# watch_v1_flex_parts_test-rotated.net
KiCad netlist of a schematic drawn in EAGLE
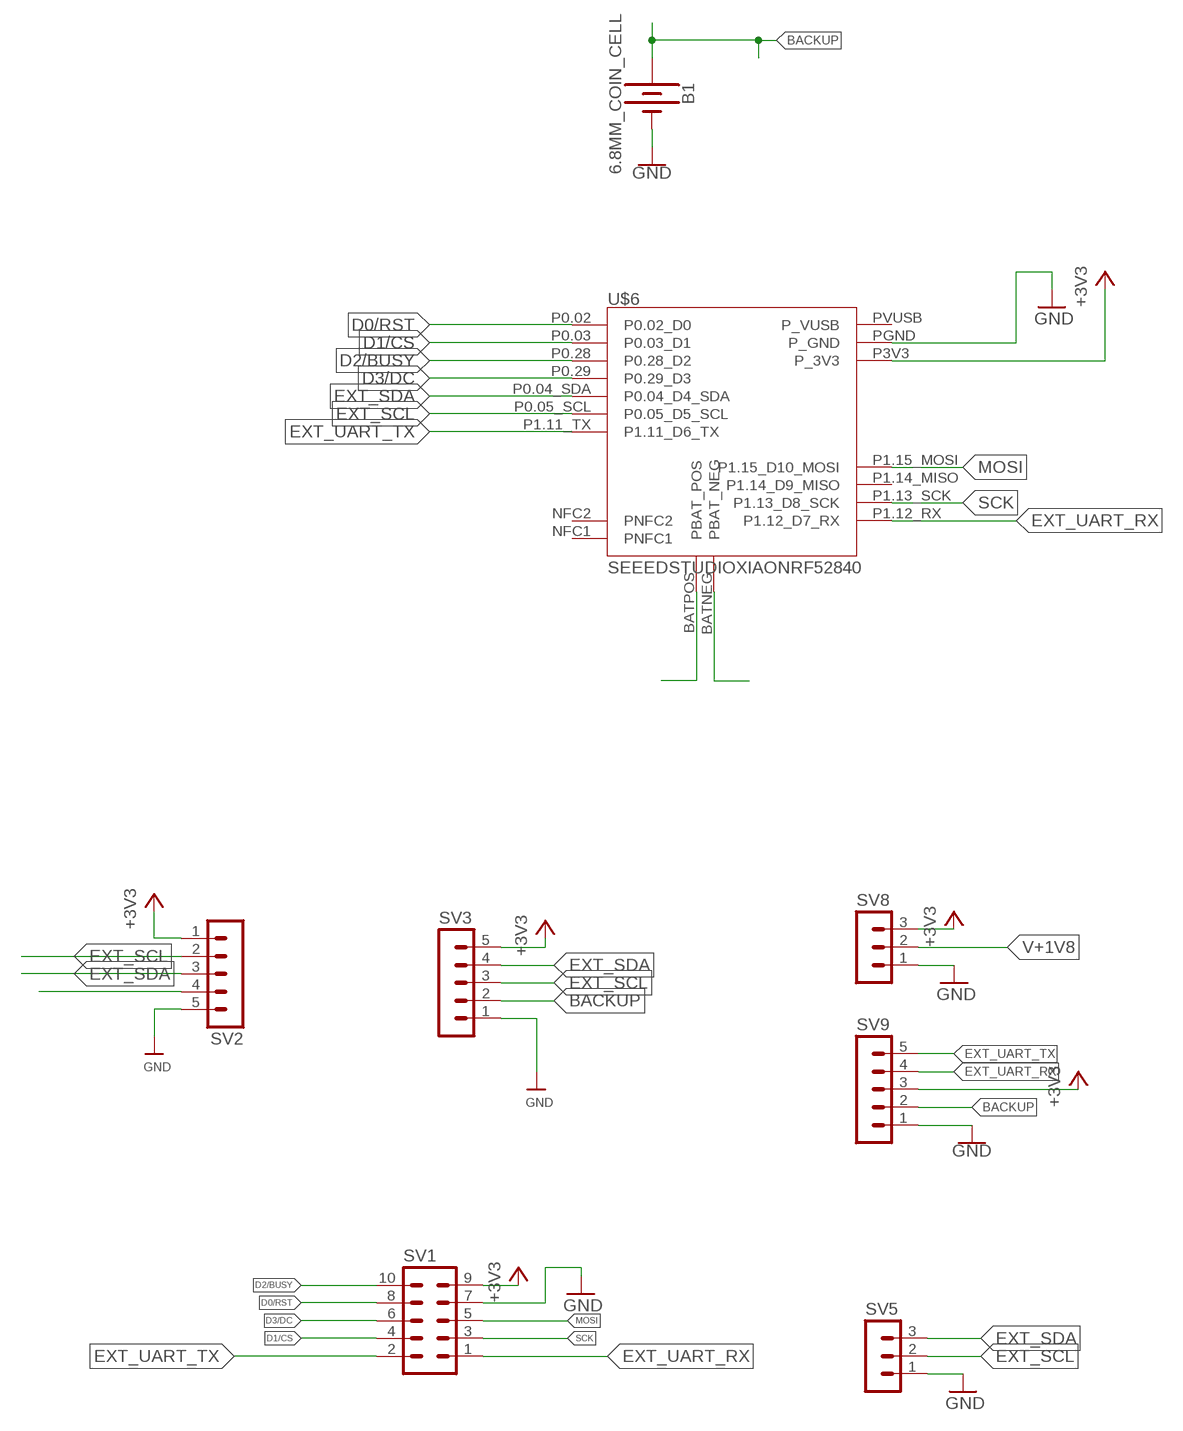
[diagram p0: schematic, sheet 1]

(export (version "E")
  (design (tool "Eeschema 10.0.6"))
  (components
    (comp (ref "B1")
      (value "6.8MM_COIN_CELL")
      (footprint "eagle-import:ML414H_IV01E")
      (libsource (lib "eagle-import") (part "ML414H_IV01E_BATTERY"))
    )
    (comp (ref "SV1")
      (value "MA05-2")
      (footprint "eagle-import:MA05-2")
      (libsource (lib "eagle-import") (part "MA05-2"))
    )
    (comp (ref "SV2")
      (value "MA05-1")
      (footprint "eagle-import:MA05-1")
      (libsource (lib "eagle-import") (part "MA05-1"))
    )
    (comp (ref "SV3")
      (value "MA05-1")
      (footprint "eagle-import:MA05-1")
      (libsource (lib "eagle-import") (part "MA05-1"))
    )
    (comp (ref "SV5")
      (value "MA03-1")
      (footprint "eagle-import:MA03-1")
      (libsource (lib "eagle-import") (part "MA03-1"))
    )
    (comp (ref "SV8")
      (value "MA03-1")
      (footprint "eagle-import:MA03-1")
      (libsource (lib "eagle-import") (part "MA03-1"))
    )
    (comp (ref "SV9")
      (value "MA05-1")
      (footprint "eagle-import:MA05-1")
      (libsource (lib "eagle-import") (part "MA05-1"))
    )
    (comp (ref "U$6")
      (value "SEEEDSTUDIOXIAONRF52840")
      (footprint "eagle-import:SEEEDSTUDIOXIAONRF52840")
      (libsource (lib "eagle-import") (part "SEEEDSTUDIOXIAONRF52840"))
    )
  )
  (nets
    (net (code "1") (name "+3V3") (class "Default")
      (node (ref "SV1") (pin "9") (pinfunction "9_9") (pintype "passive"))
      (node (ref "SV2") (pin "1") (pinfunction "1_1") (pintype "passive"))
      (node (ref "SV3") (pin "5") (pinfunction "5_5") (pintype "passive"))
      (node (ref "SV8") (pin "3") (pinfunction "3_3") (pintype "passive"))
      (node (ref "SV9") (pin "3") (pinfunction "3_3") (pintype "passive"))
      (node (ref "U$6") (pin "P3V3") (pinfunction "P_3V3_P3V3") (pintype "bidirectional"))
    )
    (net (code "2") (name "BACKUP") (class "Default")
      (node (ref "B1") (pin "+") (pinfunction "+_+") (pintype "power_in"))
      (node (ref "SV3") (pin "2") (pinfunction "2_2") (pintype "passive"))
      (node (ref "SV9") (pin "2") (pinfunction "2_2") (pintype "passive"))
    )
    (net (code "3") (name "D0{slash}RST") (class "Default")
      (node (ref "SV1") (pin "8") (pinfunction "8_8") (pintype "passive"))
      (node (ref "U$6") (pin "P0.02") (pinfunction "P0.02_D0_P0.02") (pintype "bidirectional"))
    )
    (net (code "4") (name "D1{slash}CS") (class "Default")
      (node (ref "SV1") (pin "4") (pinfunction "4_4") (pintype "passive"))
      (node (ref "U$6") (pin "P0.03") (pinfunction "P0.03_D1_P0.03") (pintype "bidirectional"))
    )
    (net (code "5") (name "D2{slash}BUSY") (class "Default")
      (node (ref "SV1") (pin "10") (pinfunction "10_10") (pintype "passive"))
      (node (ref "U$6") (pin "P0.28") (pinfunction "P0.28_D2_P0.28") (pintype "bidirectional"))
    )
    (net (code "6") (name "D3{slash}DC") (class "Default")
      (node (ref "SV1") (pin "6") (pinfunction "6_6") (pintype "passive"))
      (node (ref "U$6") (pin "P0.29") (pinfunction "P0.29_D3_P0.29") (pintype "bidirectional"))
    )
    (net (code "7") (name "EXT_SCL") (class "Default")
      (node (ref "SV2") (pin "2") (pinfunction "2_2") (pintype "passive"))
      (node (ref "SV3") (pin "3") (pinfunction "3_3") (pintype "passive"))
      (node (ref "SV5") (pin "2") (pinfunction "2_2") (pintype "passive"))
      (node (ref "U$6") (pin "P0.05_SCL") (pinfunction "P0.05_D5_SCL_P0.05_SCL") (pintype "bidirectional"))
    )
    (net (code "8") (name "EXT_SDA") (class "Default")
      (node (ref "SV2") (pin "3") (pinfunction "3_3") (pintype "passive"))
      (node (ref "SV3") (pin "4") (pinfunction "4_4") (pintype "passive"))
      (node (ref "SV5") (pin "3") (pinfunction "3_3") (pintype "passive"))
      (node (ref "U$6") (pin "P0.04_SDA") (pinfunction "P0.04_D4_SDA_P0.04_SDA") (pintype "bidirectional"))
    )
    (net (code "9") (name "EXT_UART_RX") (class "Default")
      (node (ref "SV1") (pin "1") (pinfunction "1_1") (pintype "passive"))
      (node (ref "SV9") (pin "4") (pinfunction "4_4") (pintype "passive"))
      (node (ref "U$6") (pin "P1.12_RX") (pinfunction "P1.12_D7_RX_P1.12_RX") (pintype "bidirectional"))
    )
    (net (code "10") (name "EXT_UART_TX") (class "Default")
      (node (ref "SV1") (pin "2") (pinfunction "2_2") (pintype "passive"))
      (node (ref "SV9") (pin "5") (pinfunction "5_5") (pintype "passive"))
      (node (ref "U$6") (pin "P1.11_TX") (pinfunction "P1.11_D6_TX_P1.11_TX") (pintype "bidirectional"))
    )
    (net (code "11") (name "GND") (class "Default")
      (node (ref "B1") (pin "-") (pinfunction "-_-") (pintype "power_in"))
      (node (ref "SV1") (pin "7") (pinfunction "7_7") (pintype "passive"))
      (node (ref "SV2") (pin "5") (pinfunction "5_5") (pintype "passive"))
      (node (ref "SV3") (pin "1") (pinfunction "1_1") (pintype "passive"))
      (node (ref "SV5") (pin "1") (pinfunction "1_1") (pintype "passive"))
      (node (ref "SV8") (pin "1") (pinfunction "1_1") (pintype "passive"))
      (node (ref "SV9") (pin "1") (pinfunction "1_1") (pintype "passive"))
      (node (ref "U$6") (pin "PGND") (pinfunction "P_GND_PGND") (pintype "bidirectional"))
    )
    (net (code "12") (name "MOSI") (class "Default")
      (node (ref "SV1") (pin "5") (pinfunction "5_5") (pintype "passive"))
      (node (ref "U$6") (pin "P1.15_MOSI") (pinfunction "P1.15_D10_MOSI_P1.15_MOSI") (pintype "bidirectional"))
    )
    (net (code "13") (name "SCK") (class "Default")
      (node (ref "SV1") (pin "3") (pinfunction "3_3") (pintype "passive"))
      (node (ref "U$6") (pin "P1.13_SCK") (pinfunction "P1.13_D8_SCK_P1.13_SCK") (pintype "bidirectional"))
    )
    (net (code "14") (name "V+1V8") (class "Default")
      (node (ref "SV8") (pin "2") (pinfunction "2_2") (pintype "passive"))
    )
    (net (code "15") (name "unconnected-(SV2-Pad4)") (class "Default")
      (node (ref "SV2") (pin "4") (pinfunction "4_4") (pintype "passive"))
    )
    (net (code "16") (name "unconnected-(U$6-P1.14_D9_MISO-PadP1.14_MISO)") (class "Default")
      (node (ref "U$6") (pin "P1.14_MISO") (pinfunction "P1.14_D9_MISO_P1.14_MISO") (pintype "bidirectional"))
    )
    (net (code "17") (name "unconnected-(U$6-PBAT_NEG-PadBATNEG)") (class "Default")
      (node (ref "U$6") (pin "BATNEG") (pinfunction "PBAT_NEG_BATNEG") (pintype "bidirectional"))
    )
    (net (code "18") (name "unconnected-(U$6-PBAT_POS-PadBATPOS)") (class "Default")
      (node (ref "U$6") (pin "BATPOS") (pinfunction "PBAT_POS_BATPOS") (pintype "bidirectional"))
    )
    (net (code "19") (name "unconnected-(U$6-PNFC1-PadNFC1)") (class "Default")
      (node (ref "U$6") (pin "NFC1") (pinfunction "PNFC1_NFC1") (pintype "bidirectional"))
    )
    (net (code "20") (name "unconnected-(U$6-PNFC2-PadNFC2)") (class "Default")
      (node (ref "U$6") (pin "NFC2") (pinfunction "PNFC2_NFC2") (pintype "bidirectional"))
    )
    (net (code "21") (name "unconnected-(U$6-P_VUSB-PadPVUSB)") (class "Default")
      (node (ref "U$6") (pin "PVUSB") (pinfunction "P_VUSB_PVUSB") (pintype "bidirectional"))
    )
  )
)
